# RCD_Snubber_circuit.net
KiCad netlist of a schematic drawn in Altium Designer
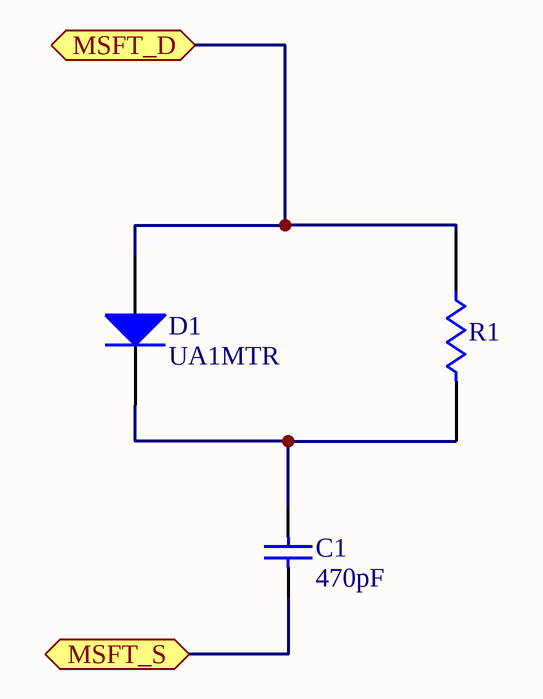
[diagram p0: RCD Snubber circuit.SchDoc]

(export (version "E")
  (design (tool "Eeschema 10.0.6"))
  (components
    (comp (ref "C1")
      (value "C2220_Generic")
      (footprint "CAP2220")
      (fields (field (name "CAPACITANCE") "470pF"))
      (libsource (lib "ucc28180-V04") (part "C2220_Generic"))
    )
    (comp (ref "D1")
      (value "UA1MTR")
      (footprint "DO-214AC")
      (description "DIODE SCHOTTKY 1KV 1A SMA")
      (fields
        (field (name "MANUFACTURER") "SMC Diode Solutions")
        (field (name "MANUFACTURER PART NUMBER") "UA1MTR")
      )
      (libsource (lib "ucc28180-V04") (part "UA1MTR"))
    )
    (comp (ref "R1")
      (value "R2512_Generic")
      (footprint "RES2512")
      (libsource (lib "ucc28180-V04") (part "R2512_Generic"))
    )
  )
  (nets
    (net (code "1") (name "/MSFT_D") (class "Default")
      (node (ref "D1") (pin "2") (pinfunction "A_2") (pintype "passive"))
      (node (ref "R1") (pin "1") (pinfunction "1_1") (pintype "passive"))
    )
    (net (code "2") (name "/MSFT_S") (class "Default")
      (node (ref "C1") (pin "1") (pinfunction "1_1") (pintype "passive"))
    )
    (net (code "3") (name "Net-(D1-K)") (class "Default")
      (node (ref "C1") (pin "2") (pinfunction "2_2") (pintype "passive"))
      (node (ref "D1") (pin "1") (pinfunction "K_1") (pintype "passive"))
      (node (ref "R1") (pin "2") (pinfunction "2_2") (pintype "passive"))
    )
  )
)
